# lpm.net
KiCad netlist of a schematic drawn in EAGLE
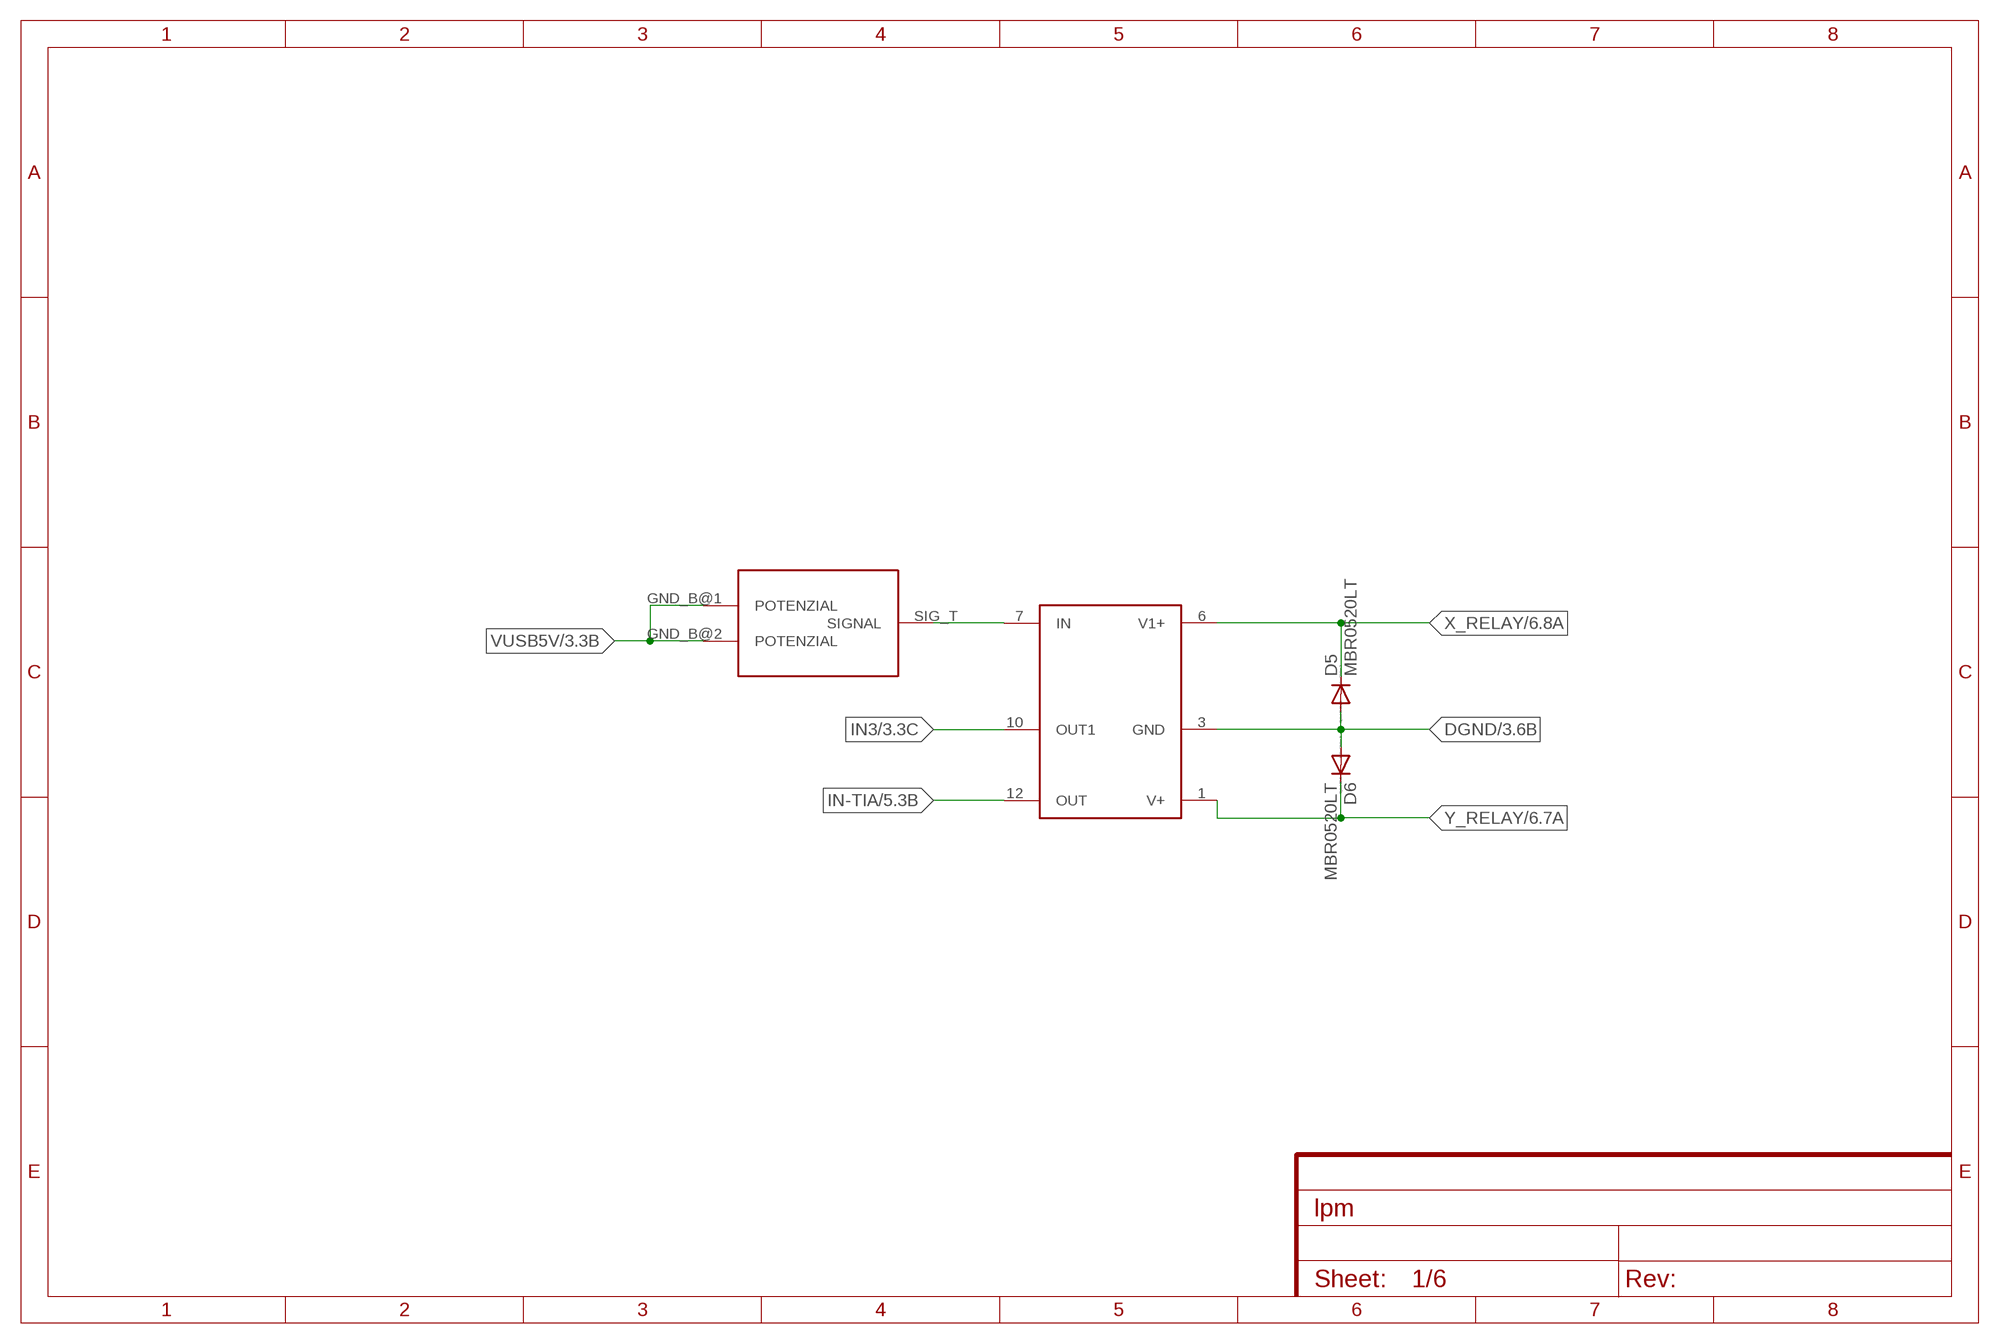
[diagram p0: schematic, sheet 1]
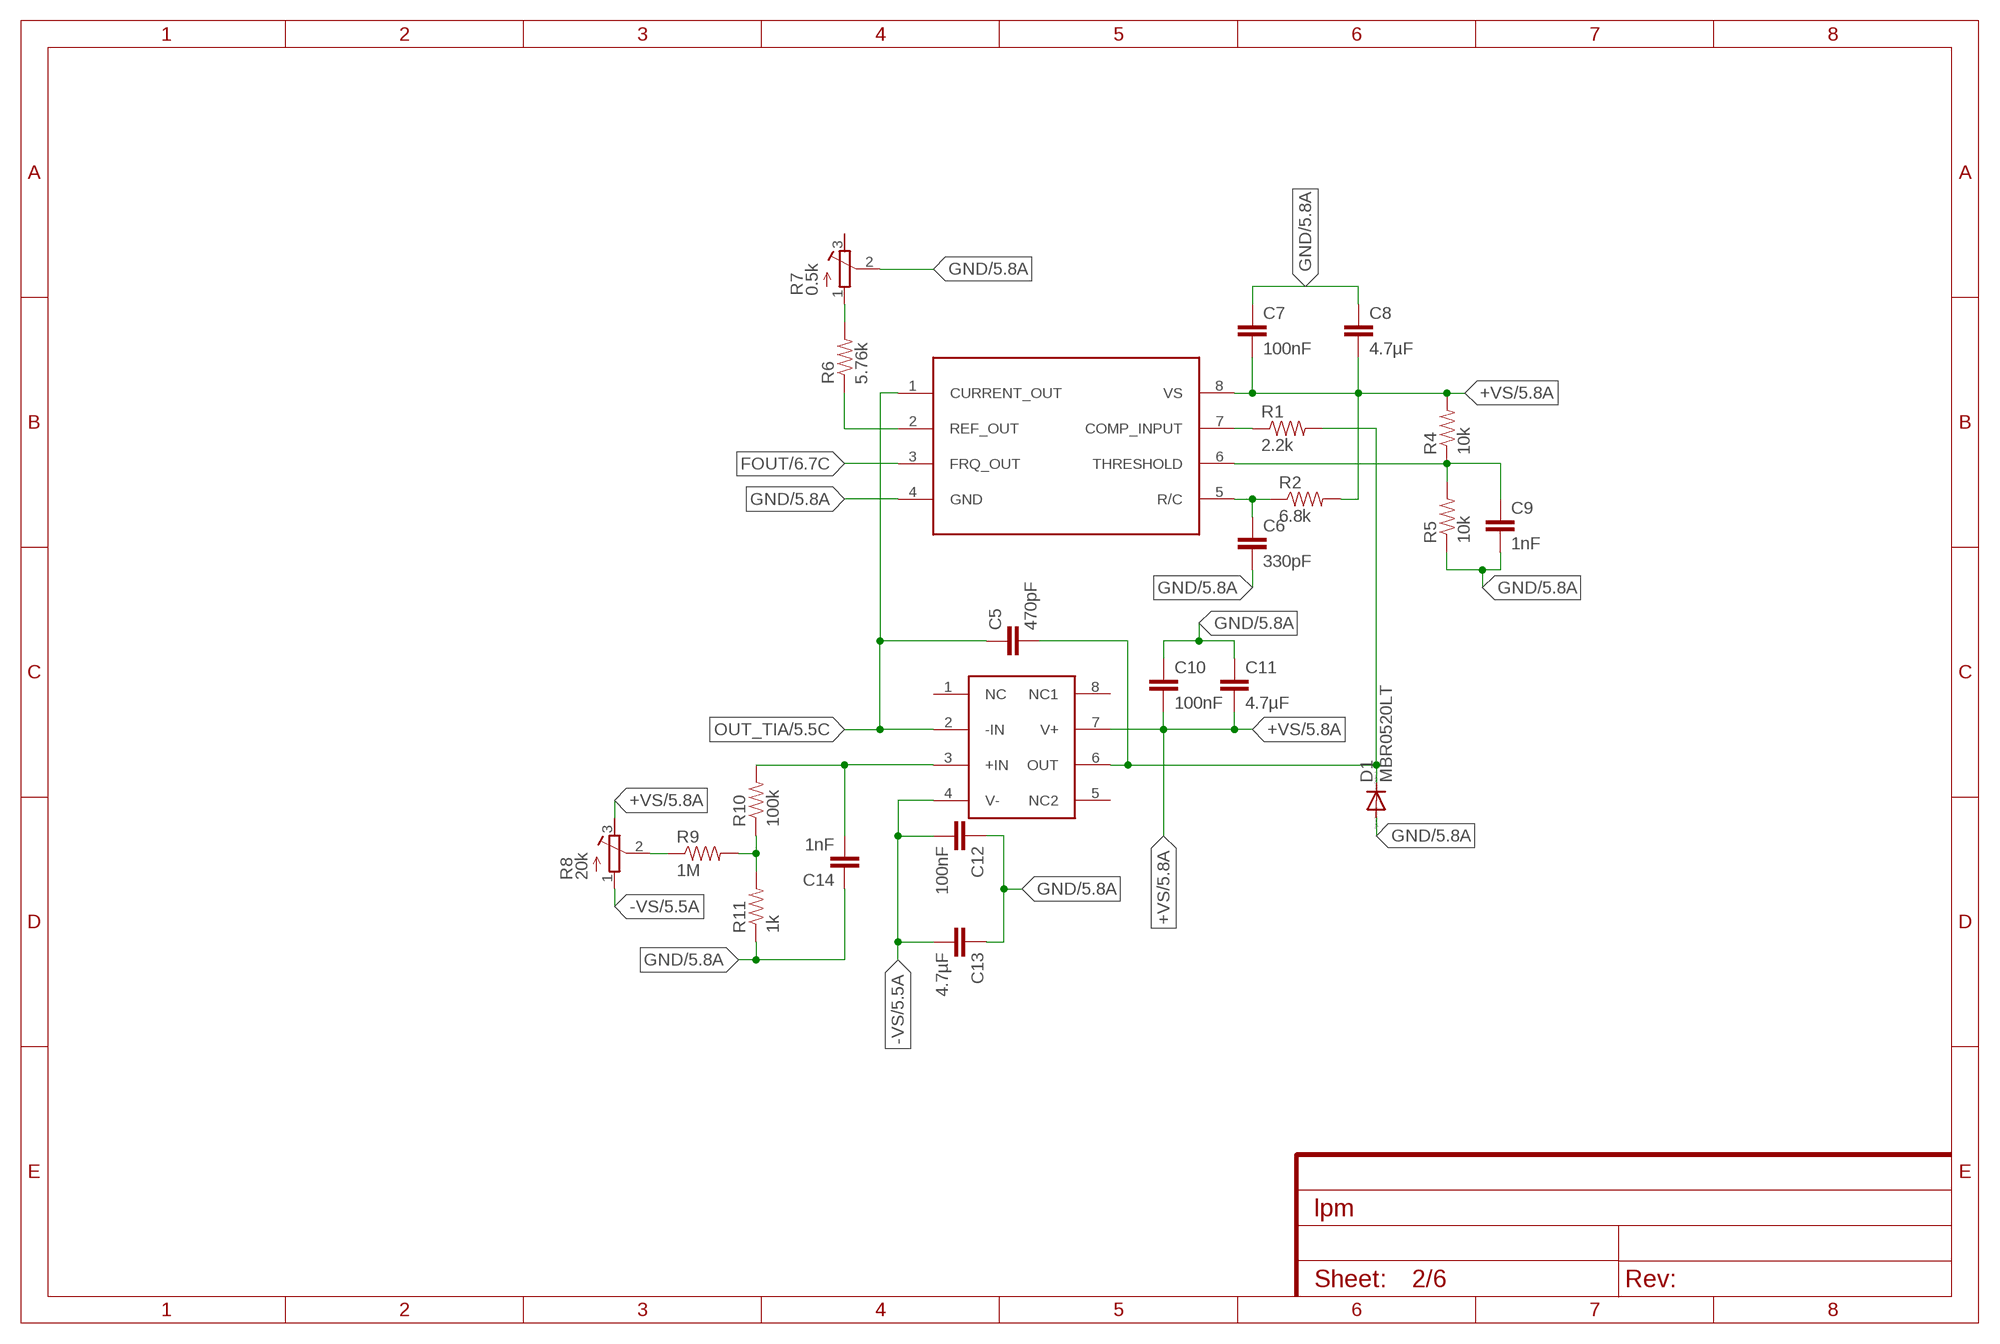
[diagram p1: schematic, sheet 2]
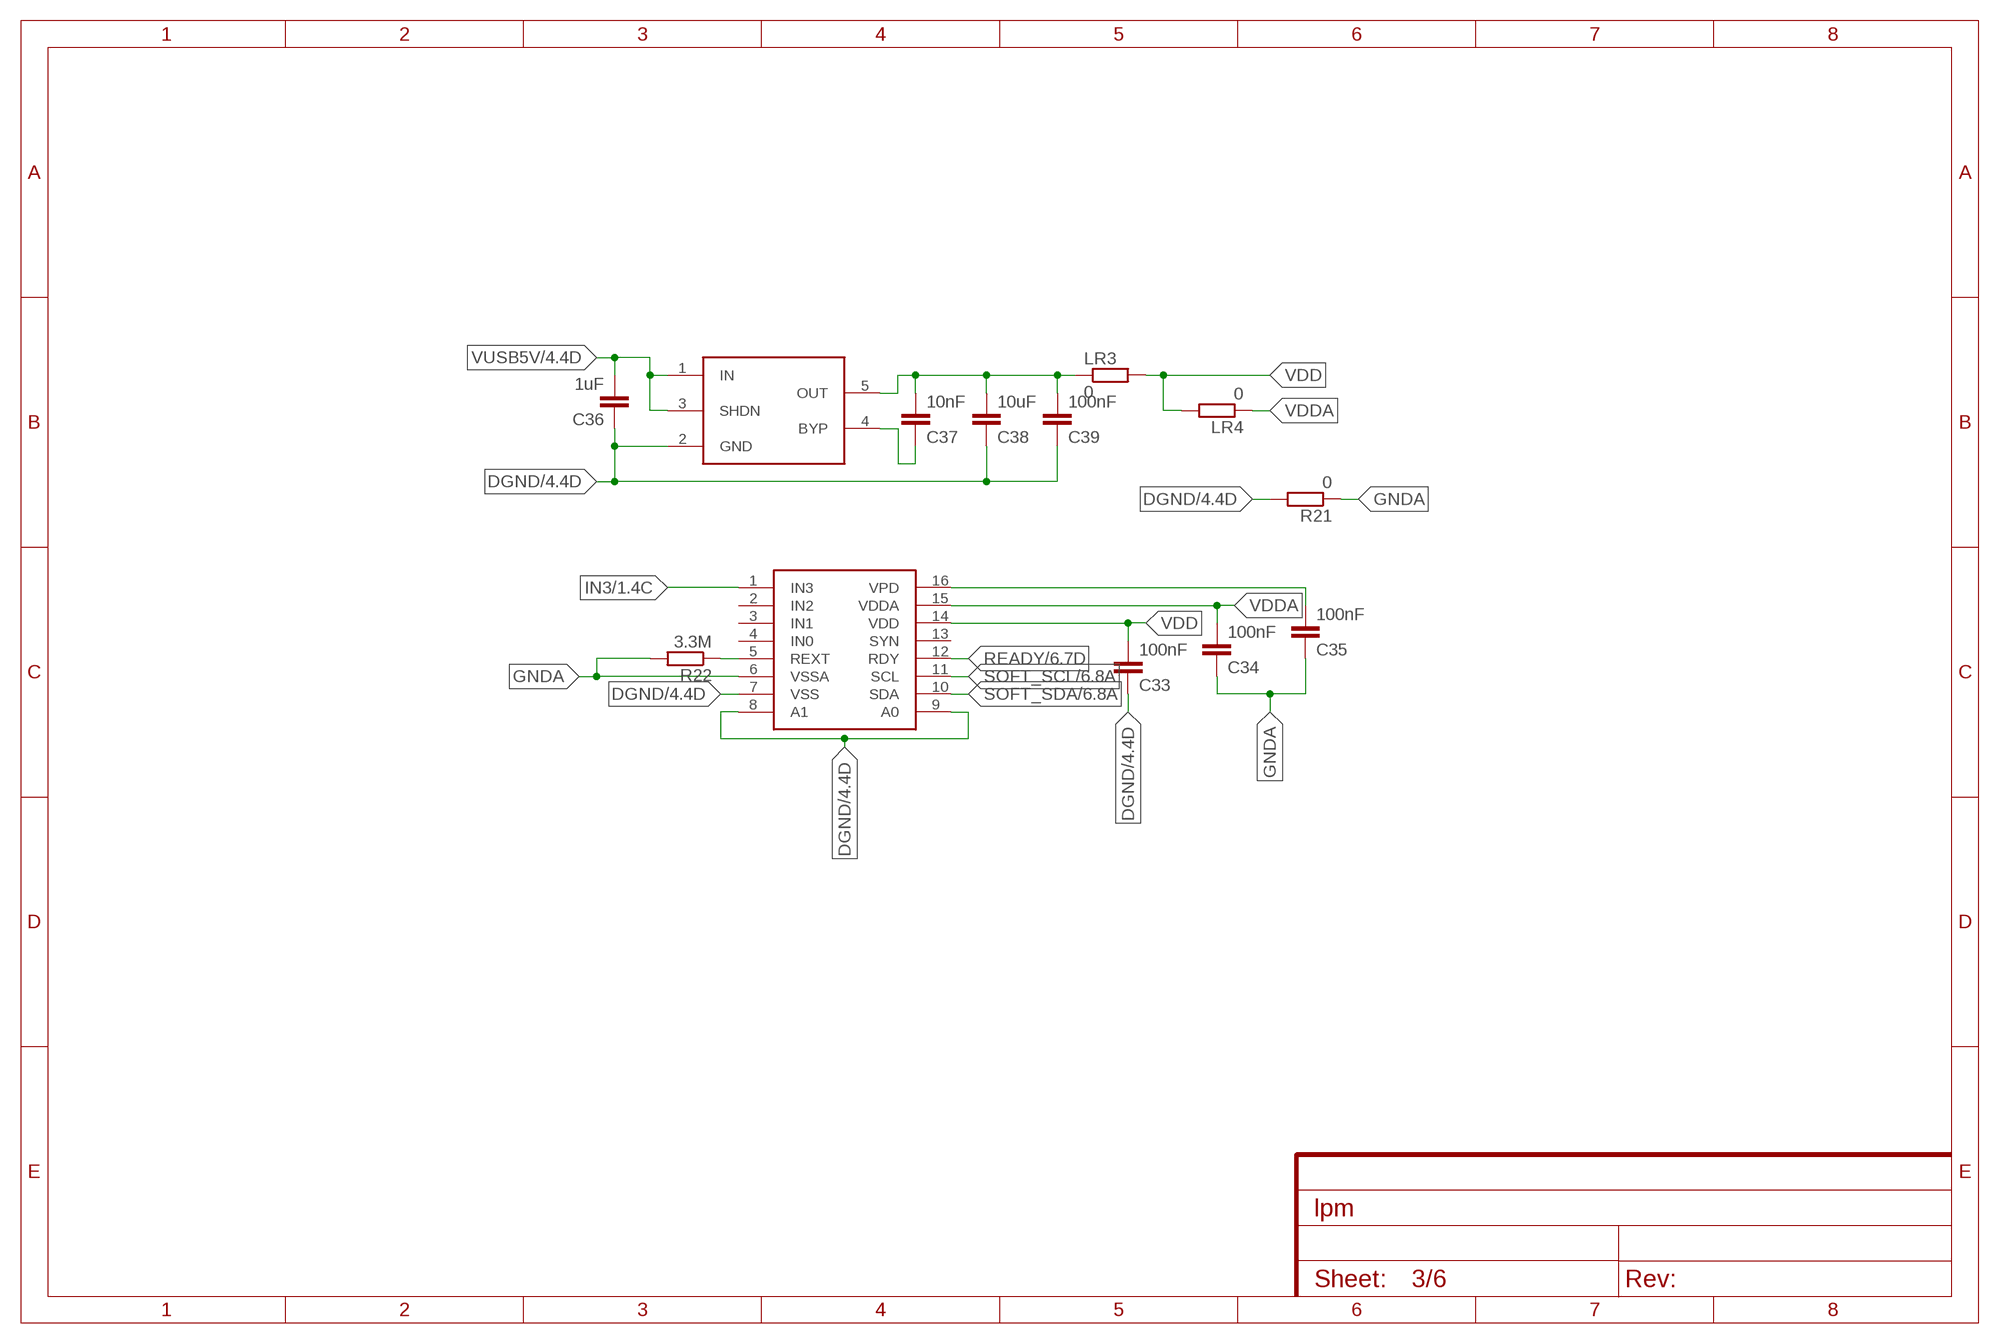
[diagram p2: schematic, sheet 3]
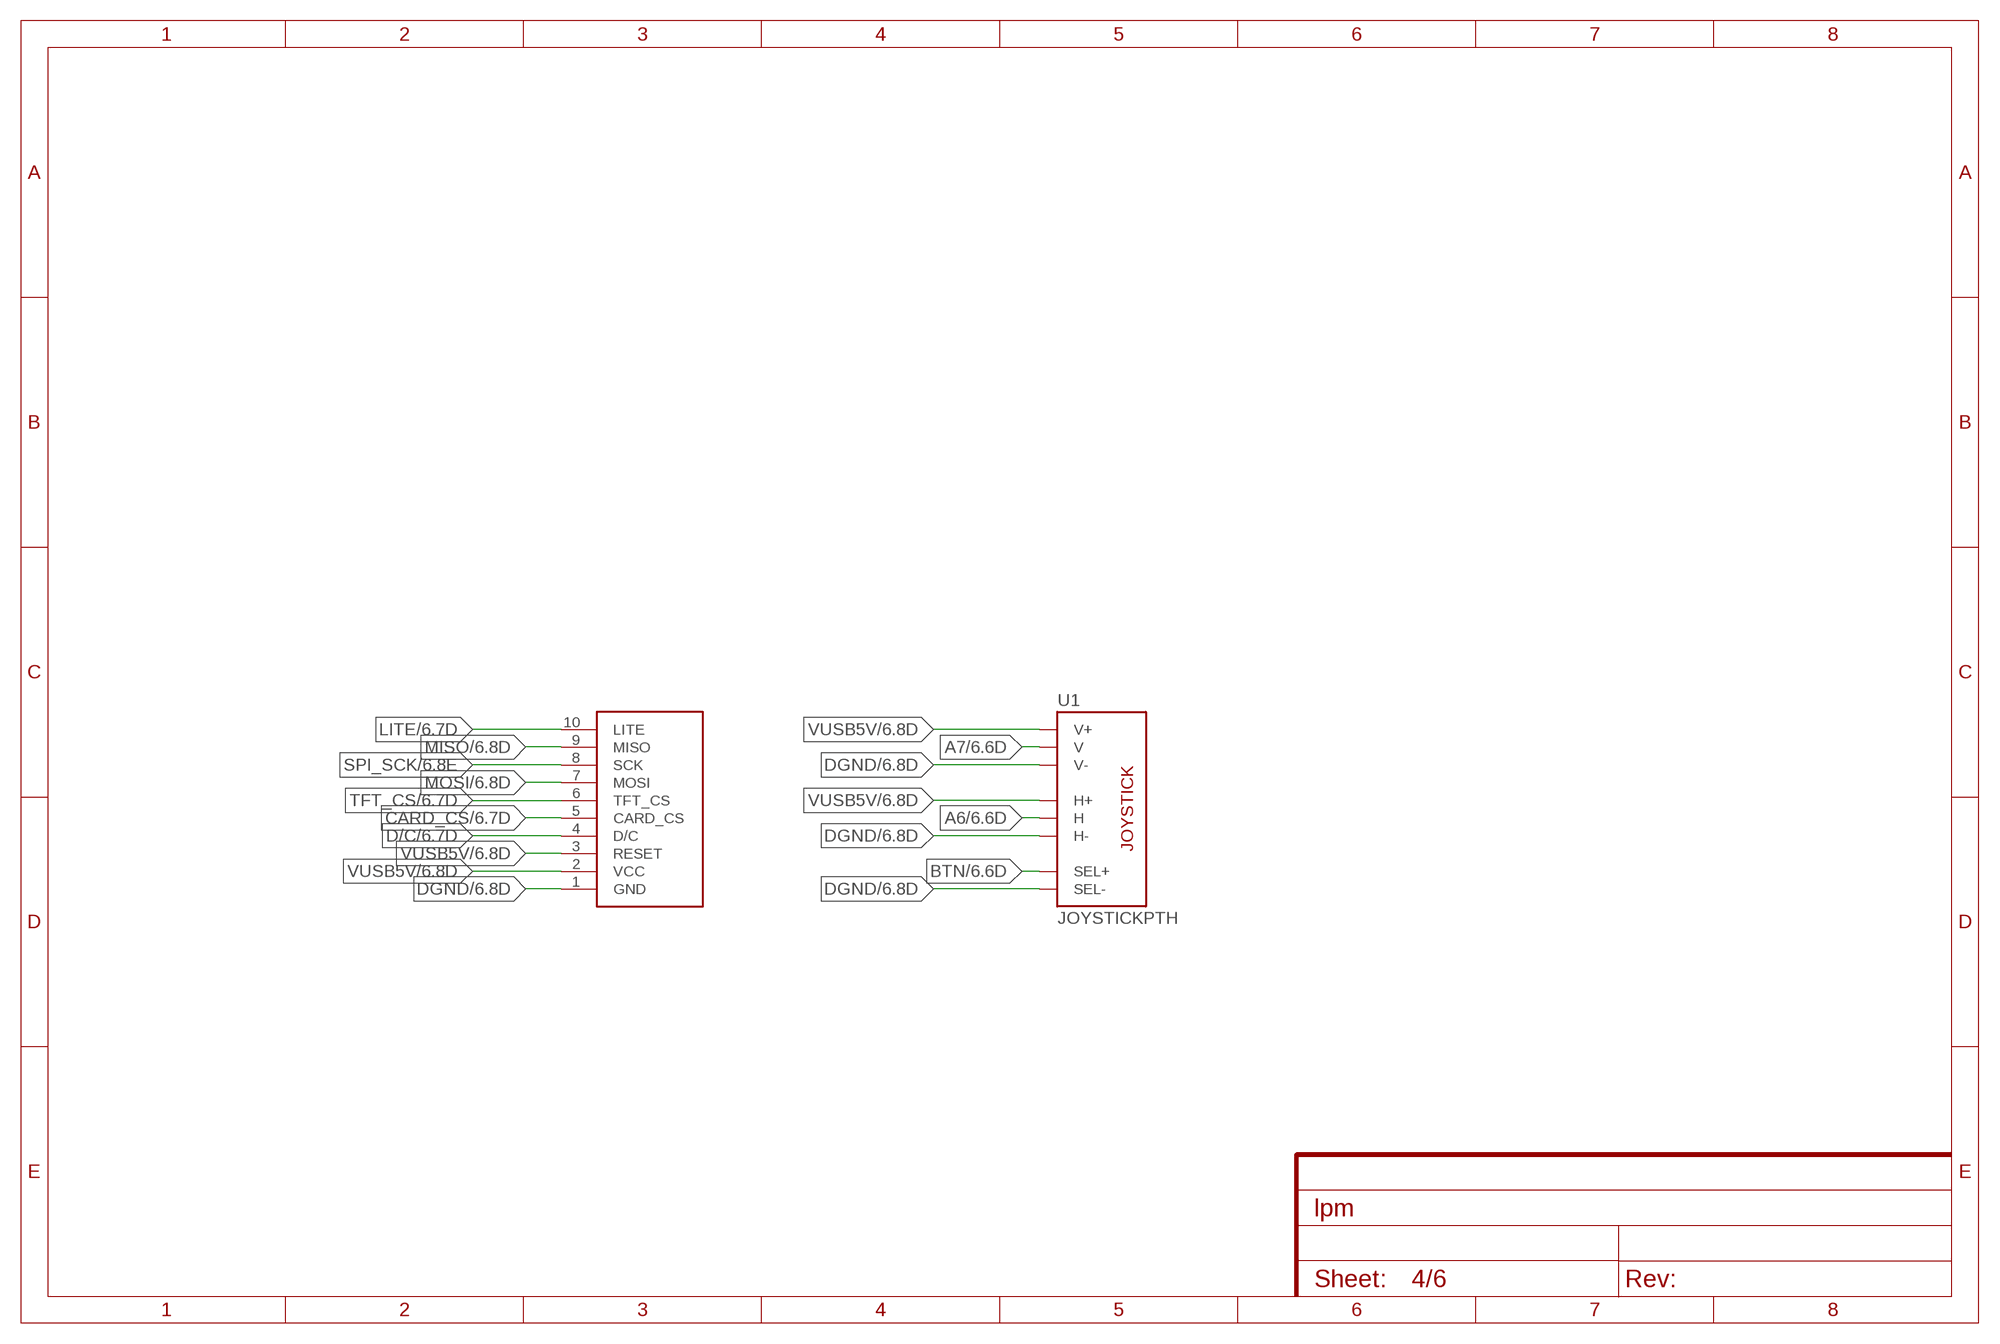
[diagram p3: schematic, sheet 4]
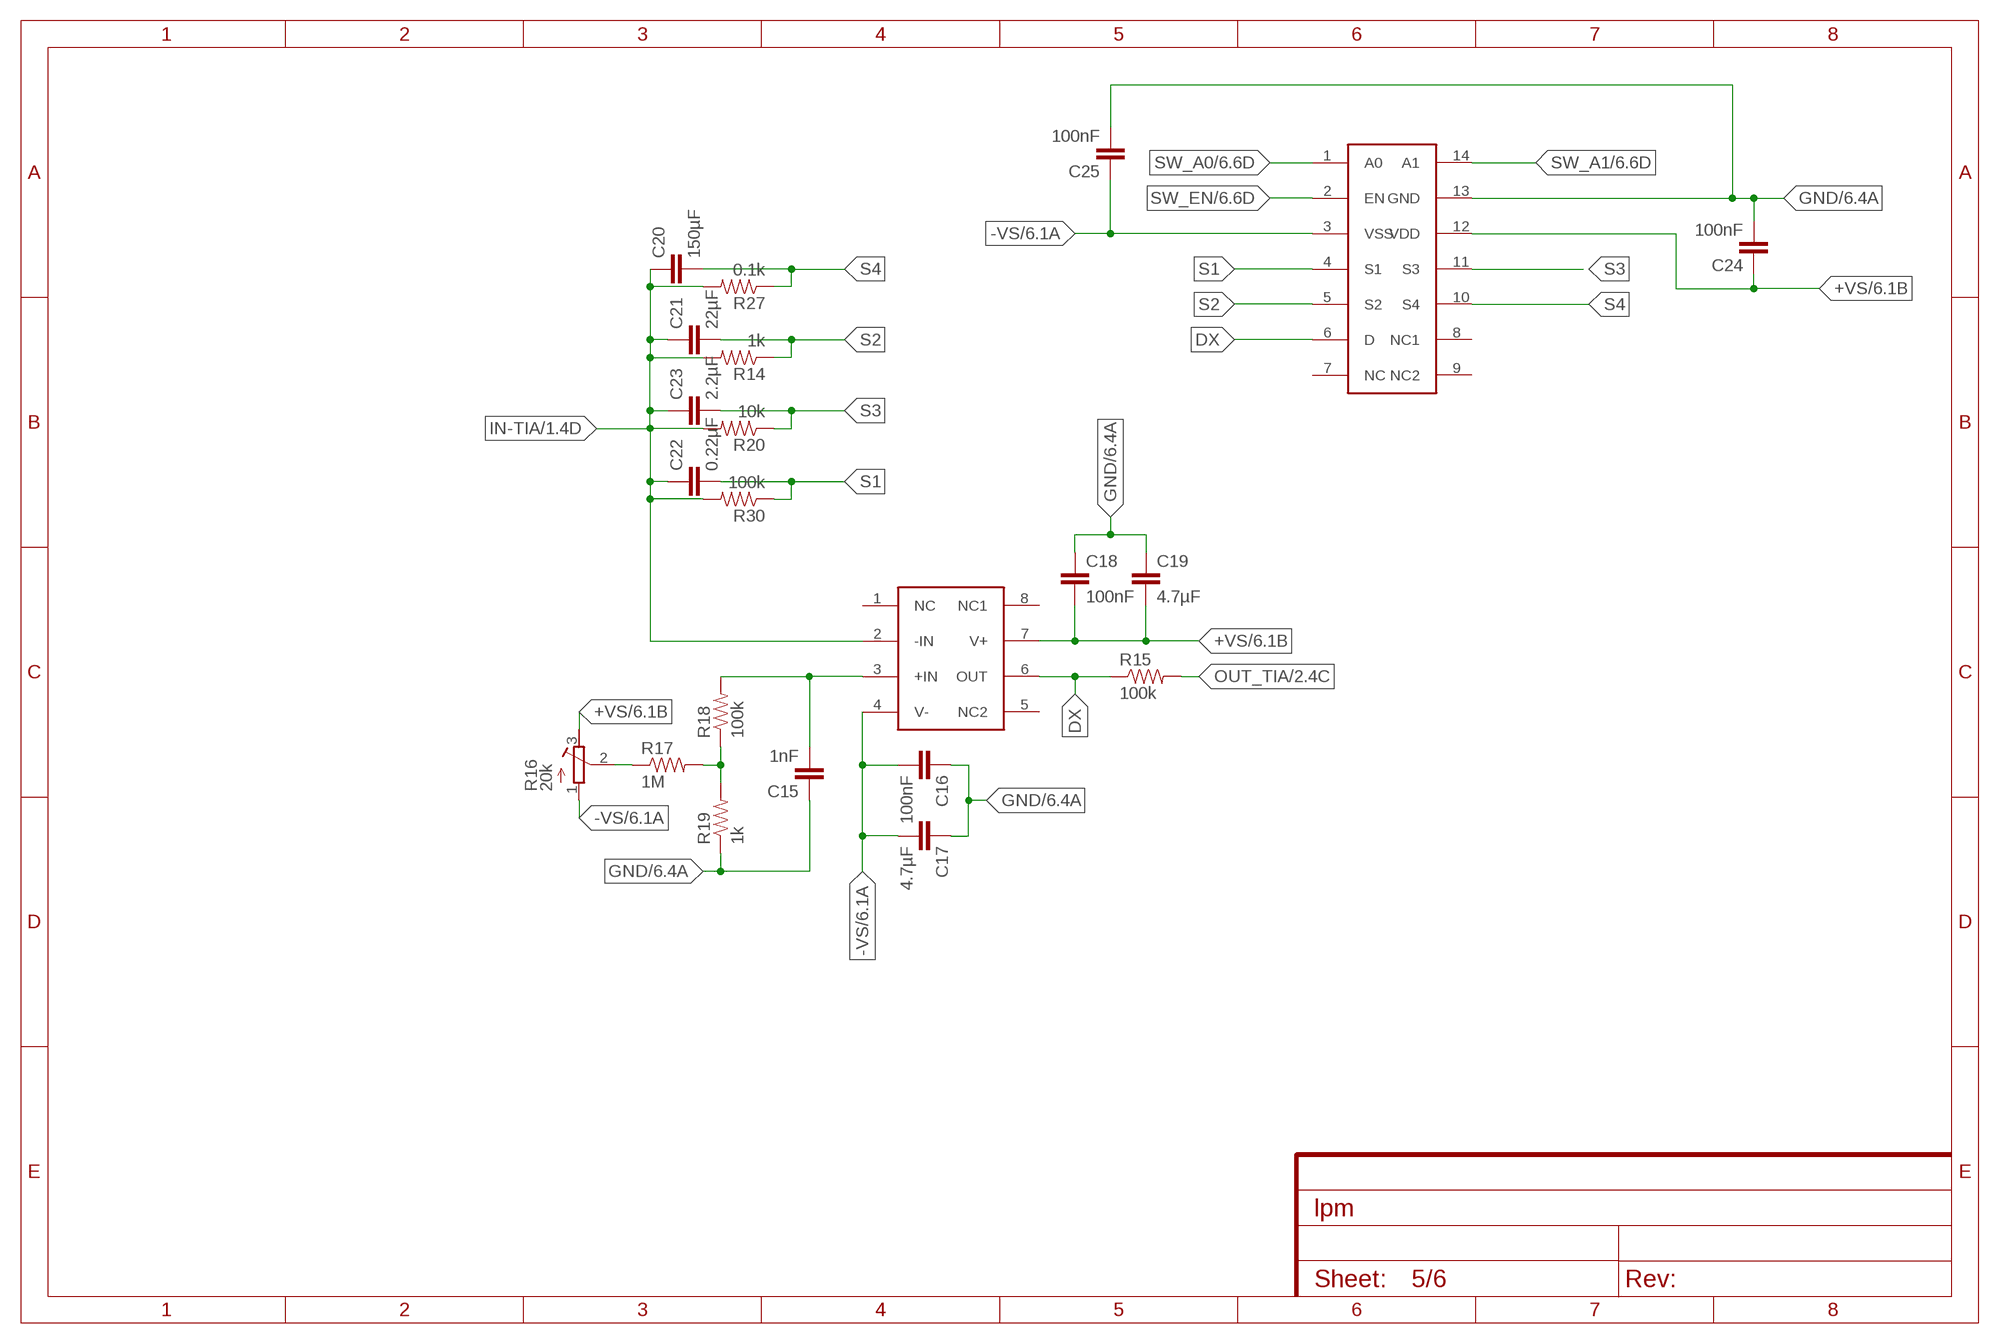
[diagram p4: schematic, sheet 5]
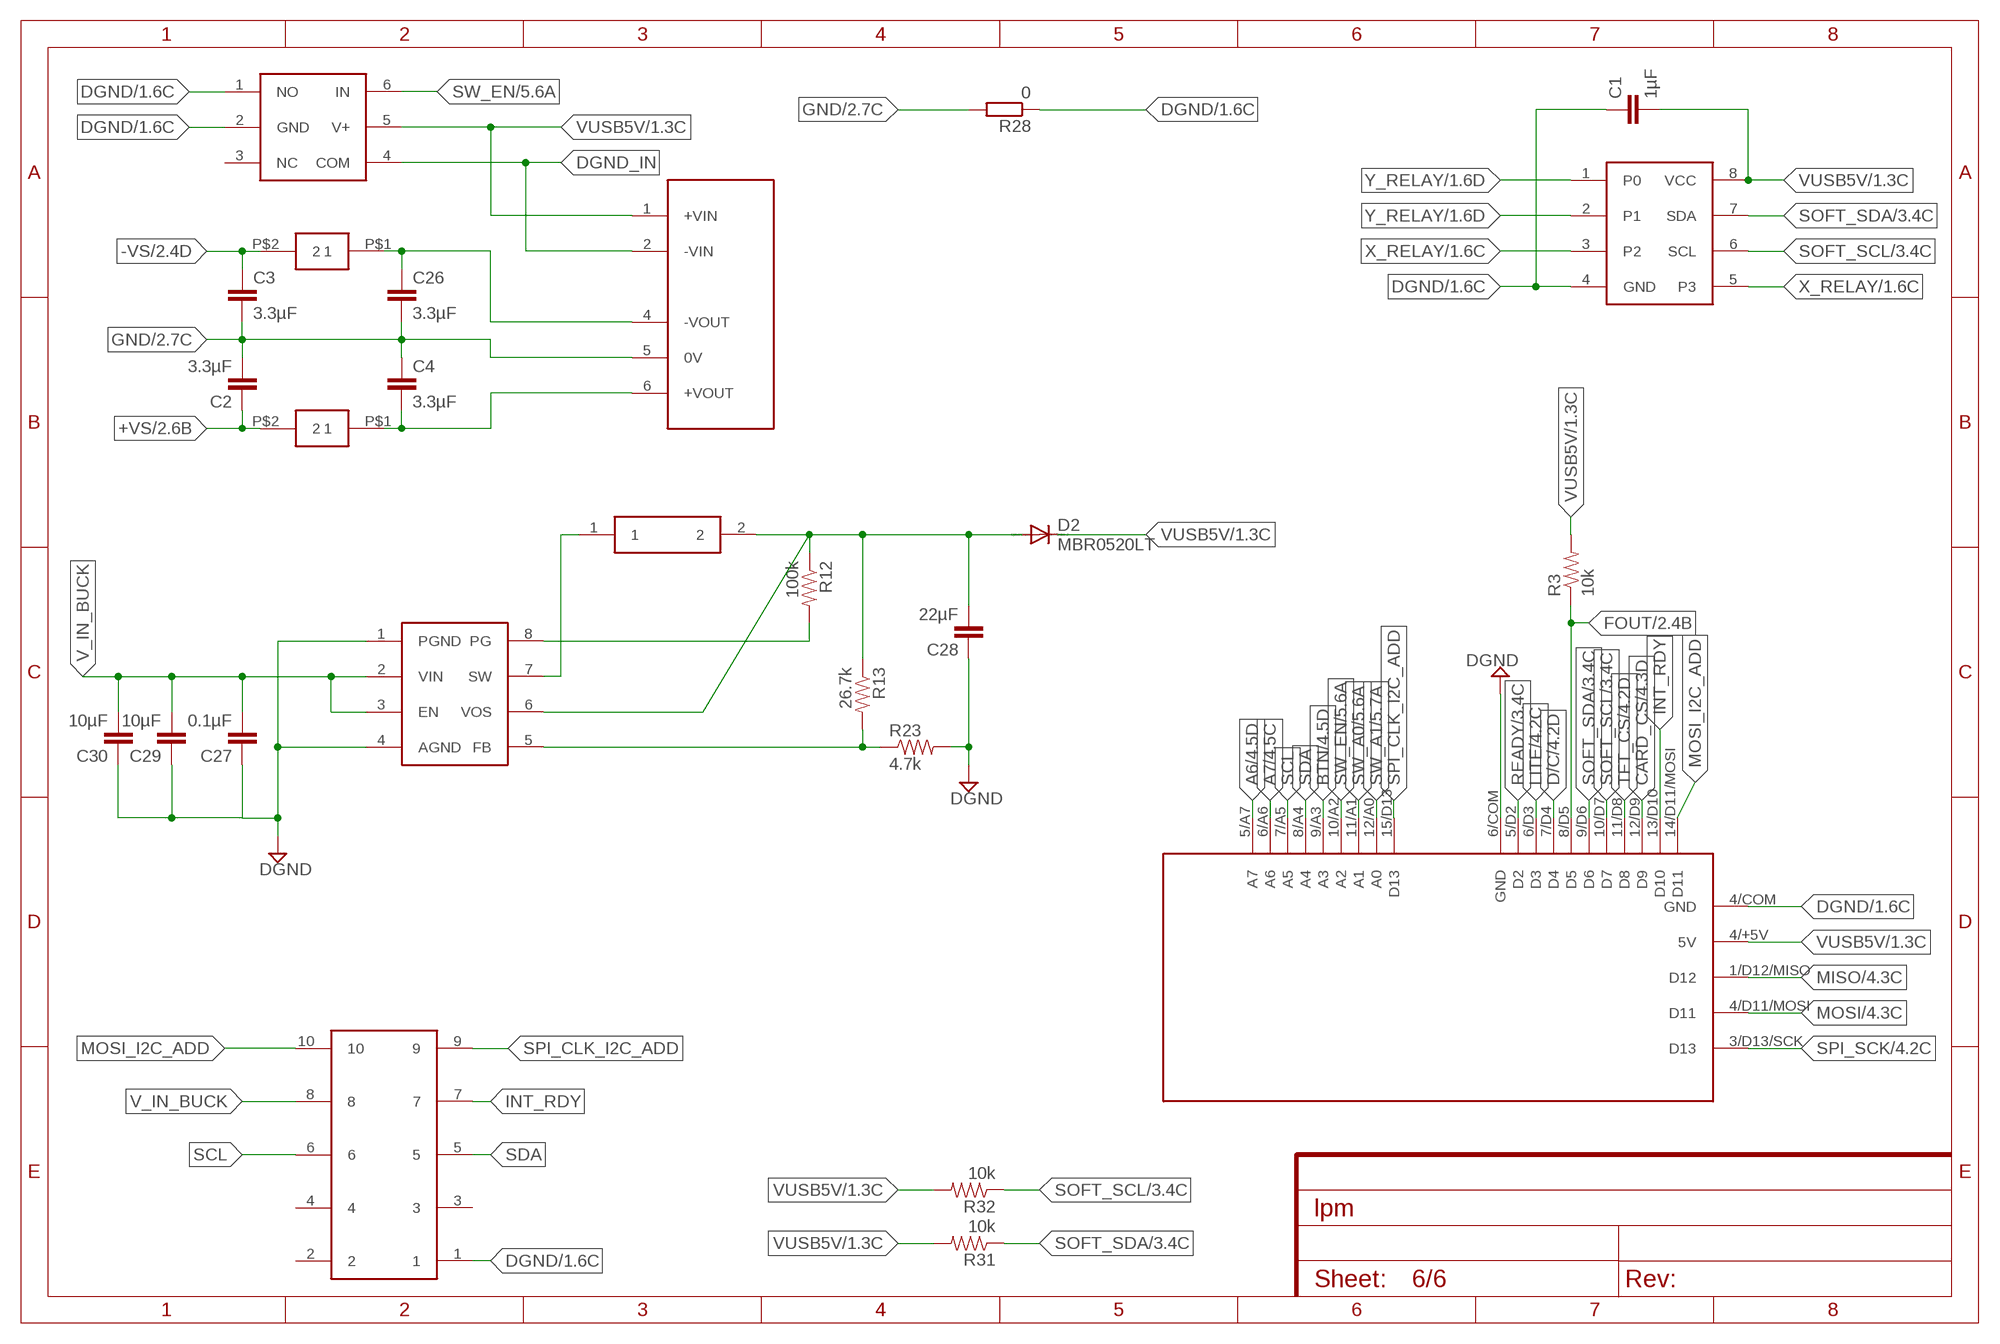
[diagram p5: schematic, sheet 6]

(export (version "E")
  (design (tool "Eeschema 10.0.6"))
  (components
    (comp (ref "C1")
      (value "1µF")
      (footprint "eagle-import:C0603K")
      (libsource (lib "eagle-import") (part "C-EUC0603K"))
    )
    (comp (ref "C2")
      (value "3.3µF")
      (footprint "eagle-import:C0603K")
      (libsource (lib "eagle-import") (part "C-EUC0603K"))
    )
    (comp (ref "C3")
      (value "3.3µF")
      (footprint "eagle-import:C0603K")
      (libsource (lib "eagle-import") (part "C-EUC0603K"))
    )
    (comp (ref "C4")
      (value "3.3µF")
      (footprint "eagle-import:C0603K")
      (libsource (lib "eagle-import") (part "C-EUC0603K"))
    )
    (comp (ref "C26")
      (value "3.3µF")
      (footprint "eagle-import:C0603K")
      (libsource (lib "eagle-import") (part "C-EUC0603K"))
    )
    (comp (ref "C27")
      (value "0.1µF")
      (footprint "eagle-import:C0603K")
      (libsource (lib "eagle-import") (part "C-EUC0603K"))
    )
    (comp (ref "C28")
      (value "22µF")
      (footprint "eagle-import:C0603K")
      (libsource (lib "eagle-import") (part "C-EUC0603K"))
    )
    (comp (ref "C29")
      (value "10µF")
      (footprint "eagle-import:C0603K")
      (libsource (lib "eagle-import") (part "C-EUC0603K"))
    )
    (comp (ref "C30")
      (value "10µF")
      (footprint "eagle-import:C0603K")
      (libsource (lib "eagle-import") (part "C-EUC0603K"))
    )
    (comp (ref "D2")
      (value "MBR0520LT")
      (footprint "eagle-import:SOD123")
      (libsource (lib "eagle-import") (part "MBR0520LT"))
    )
    (comp (ref "R3")
      (value "10k")
      (footprint "eagle-import:0603-RES")
      (libsource (lib "eagle-import") (part "RESISTOR0603-RES"))
    )
    (comp (ref "R12")
      (value "100k")
      (footprint "eagle-import:0603-RES")
      (libsource (lib "eagle-import") (part "RESISTOR0603-RES"))
    )
    (comp (ref "R13")
      (value "26.7k")
      (footprint "eagle-import:0603-RES")
      (libsource (lib "eagle-import") (part "RESISTOR0603-RES"))
    )
    (comp (ref "R23")
      (value "4.7k")
      (footprint "eagle-import:0603-RES")
      (libsource (lib "eagle-import") (part "RESISTOR0603-RES"))
    )
    (comp (ref "R28")
      (value "0")
      (footprint "eagle-import:R0603")
      (libsource (lib "eagle-import") (part "resistor_R-EU_R0603"))
    )
    (comp (ref "R31")
      (value "10k")
      (footprint "eagle-import:0603-RES")
      (libsource (lib "eagle-import") (part "RESISTOR0603-RES"))
    )
    (comp (ref "R32")
      (value "10k")
      (footprint "eagle-import:0603-RES")
      (libsource (lib "eagle-import") (part "RESISTOR0603-RES"))
    )
    (comp (ref "U$2")
      (value "KMP_100µH")
      (footprint "eagle-import:KMP")
      (libsource (lib "eagle-import") (part "KMP"))
    )
    (comp (ref "U$3")
      (value "HEADER_10POL")
      (footprint "eagle-import:BOX_HEADER_2.54MM")
      (libsource (lib "eagle-import") (part "HEADER_10POL"))
    )
    (comp (ref "U$4")
      (value "KMP_100µH")
      (footprint "eagle-import:KMP")
      (libsource (lib "eagle-import") (part "KMP"))
    )
    (comp (ref "U$6")
      (value "TS5A3159A")
      (footprint "eagle-import:SOT23-6")
      (libsource (lib "eagle-import") (part "TS5A3159A"))
    )
    (comp (ref "U$7")
      (value "0")
      (footprint "eagle-import:SOIC8_4.90MMX3.91MM")
      (libsource (lib "eagle-import") (part "PCA9536"))
    )
    (comp (ref "U$9")
      (value "LPS3015")
      (footprint "eagle-import:LPS3015")
      (libsource (lib "eagle-import") (part "LPS3015"))
    )
    (comp (ref "U$11")
      (value "NMA0515SC")
      (footprint "eagle-import:SIP7")
      (libsource (lib "eagle-import") (part "NMA0515SC"))
    )
    (comp (ref "U$13")
      (value "NANO_V2")
      (footprint "eagle-import:NANO_V2")
      (libsource (lib "eagle-import") (part "NANO_V2"))
    )
    (comp (ref "U$14")
      (value "TPS62160")
      (footprint "eagle-import:POWER-SOP8")
      (libsource (lib "eagle-import") (part "TPS62160"))
    )
    (comp (ref "C15")
      (value "1nF")
      (footprint "eagle-import:C0603K")
      (libsource (lib "eagle-import") (part "C-EUC0603K"))
    )
    (comp (ref "C16")
      (value "100nF")
      (footprint "eagle-import:C0603K")
      (libsource (lib "eagle-import") (part "C-EUC0603K"))
    )
    (comp (ref "C17")
      (value "4.7µF")
      (footprint "eagle-import:C0603K")
      (libsource (lib "eagle-import") (part "C-EUC0603K"))
    )
    (comp (ref "C18")
      (value "100nF")
      (footprint "eagle-import:C0603K")
      (libsource (lib "eagle-import") (part "C-EUC0603K"))
    )
    (comp (ref "C19")
      (value "4.7µF")
      (footprint "eagle-import:C0603K")
      (libsource (lib "eagle-import") (part "C-EUC0603K"))
    )
    (comp (ref "C20")
      (value "150µF")
      (footprint "eagle-import:C1206")
      (libsource (lib "eagle-import") (part "C-EUC1206"))
    )
    (comp (ref "C21")
      (value "22µF")
      (footprint "eagle-import:C0805")
      (libsource (lib "eagle-import") (part "C-EUC0805"))
    )
    (comp (ref "C22")
      (value "0.22µF")
      (footprint "eagle-import:C0603")
      (libsource (lib "eagle-import") (part "C-EUC0603"))
    )
    (comp (ref "C23")
      (value "2.2µF")
      (footprint "eagle-import:C0805")
      (libsource (lib "eagle-import") (part "C-EUC0805"))
    )
    (comp (ref "C24")
      (value "100nF")
      (footprint "eagle-import:C0603K")
      (libsource (lib "eagle-import") (part "C-EUC0603K"))
    )
    (comp (ref "C25")
      (value "100nF")
      (footprint "eagle-import:C0603K")
      (libsource (lib "eagle-import") (part "C-EUC0603K"))
    )
    (comp (ref "R14")
      (value "1k")
      (footprint "eagle-import:0603-RES")
      (libsource (lib "eagle-import") (part "RESISTOR0603-RES"))
    )
    (comp (ref "R15")
      (value "100k")
      (footprint "eagle-import:0603-RES")
      (libsource (lib "eagle-import") (part "RESISTOR0603-RES"))
    )
    (comp (ref "R16")
      (value "20k")
      (footprint "eagle-import:RTRIMTS63Y")
      (libsource (lib "eagle-import") (part "R-TRIMMTS63Y"))
    )
    (comp (ref "R17")
      (value "1M")
      (footprint "eagle-import:0603-RES")
      (libsource (lib "eagle-import") (part "RESISTOR0603-RES"))
    )
    (comp (ref "R18")
      (value "100k")
      (footprint "eagle-import:0603-RES")
      (libsource (lib "eagle-import") (part "RESISTOR0603-RES"))
    )
    (comp (ref "R19")
      (value "1k")
      (footprint "eagle-import:0603-RES")
      (libsource (lib "eagle-import") (part "RESISTOR0603-RES"))
    )
    (comp (ref "R20")
      (value "10k")
      (footprint "eagle-import:0603-RES")
      (libsource (lib "eagle-import") (part "RESISTOR0603-RES"))
    )
    (comp (ref "R27")
      (value "0.1k")
      (footprint "eagle-import:1206")
      (libsource (lib "eagle-import") (part "RESISTOR1206"))
    )
    (comp (ref "R30")
      (value "100k")
      (footprint "eagle-import:0603-RES")
      (libsource (lib "eagle-import") (part "RESISTOR0603-RES"))
    )
    (comp (ref "U$1")
      (value "ADG1404")
      (footprint "eagle-import:TSSOP14-0.65-5X4.4MM")
      (libsource (lib "eagle-import") (part "ADG1404"))
    )
    (comp (ref "U$12")
      (value "OPA191")
      (footprint "eagle-import:SOIC8_4.90MMX3.91MM")
      (libsource (lib "eagle-import") (part "OPA191"))
    )
    (comp (ref "C33")
      (value "100nF")
      (footprint "eagle-import:C0603")
      (libsource (lib "eagle-import") (part "C-EUC0603"))
    )
    (comp (ref "C34")
      (value "100nF")
      (footprint "eagle-import:C0603")
      (libsource (lib "eagle-import") (part "C-EUC0603"))
    )
    (comp (ref "C35")
      (value "100nF")
      (footprint "eagle-import:C0603")
      (libsource (lib "eagle-import") (part "C-EUC0603"))
    )
    (comp (ref "C36")
      (value "1uF")
      (footprint "eagle-import:C0603")
      (libsource (lib "eagle-import") (part "C-EUC0603"))
    )
    (comp (ref "C37")
      (value "10nF")
      (footprint "eagle-import:C0603")
      (libsource (lib "eagle-import") (part "C-EUC0603"))
    )
    (comp (ref "C38")
      (value "10uF")
      (footprint "eagle-import:C0603")
      (libsource (lib "eagle-import") (part "C-EUC0603"))
    )
    (comp (ref "C39")
      (value "100nF")
      (footprint "eagle-import:C0603")
      (libsource (lib "eagle-import") (part "C-EUC0603"))
    )
    (comp (ref "LDO1")
      (value "LT1761")
      (footprint "eagle-import:TSOT23-5")
      (libsource (lib "eagle-import") (part "LT1761"))
    )
    (comp (ref "LR3")
      (value "0")
      (footprint "eagle-import:R0603")
      (libsource (lib "eagle-import") (part "R-EU_R0603"))
    )
    (comp (ref "LR4")
      (value "0")
      (footprint "eagle-import:R0603")
      (libsource (lib "eagle-import") (part "R-EU_R0603"))
    )
    (comp (ref "MCDC01")
      (value "MCDC04")
      (footprint "eagle-import:SSOP16")
      (libsource (lib "eagle-import") (part "MCDC04"))
    )
    (comp (ref "R21")
      (value "0")
      (footprint "eagle-import:R0603")
      (libsource (lib "eagle-import") (part "R-EU_R0603"))
    )
    (comp (ref "R22")
      (value "3.3M")
      (footprint "eagle-import:R0603")
      (libsource (lib "eagle-import") (part "R-EU_R0603"))
    )
    (comp (ref "D5")
      (value "MBR0520LT")
      (footprint "eagle-import:SOD123")
      (libsource (lib "eagle-import") (part "MBR0520LT"))
    )
    (comp (ref "D6")
      (value "MBR0520LT")
      (footprint "eagle-import:SOD123")
      (libsource (lib "eagle-import") (part "MBR0520LT"))
    )
    (comp (ref "RELAY")
      (value "DS1E")
      (footprint "eagle-import:DIP12_8MM_X_13MM_DS1E")
      (libsource (lib "eagle-import") (part "DS1E"))
    )
    (comp (ref "U$8")
      (value "SMA_RAND")
      (footprint "eagle-import:SMA-RAND-PRINT")
      (libsource (lib "eagle-import") (part "SMA_RAND"))
    )
    (comp (ref "C5")
      (value "470pF")
      (footprint "eagle-import:0603-CAP")
      (libsource (lib "eagle-import") (part "CAP0603-CAP"))
    )
    (comp (ref "C6")
      (value "330pF")
      (footprint "eagle-import:C0603K")
      (libsource (lib "eagle-import") (part "C-EUC0603K"))
    )
    (comp (ref "C7")
      (value "100nF")
      (footprint "eagle-import:C0603K")
      (libsource (lib "eagle-import") (part "C-EUC0603K"))
    )
    (comp (ref "C8")
      (value "4.7µF")
      (footprint "eagle-import:C0603K")
      (libsource (lib "eagle-import") (part "C-EUC0603K"))
    )
    (comp (ref "C9")
      (value "1nF")
      (footprint "eagle-import:C0603K")
      (libsource (lib "eagle-import") (part "C-EUC0603K"))
    )
    (comp (ref "C10")
      (value "100nF")
      (footprint "eagle-import:C0603K")
      (libsource (lib "eagle-import") (part "C-EUC0603K"))
    )
    (comp (ref "C11")
      (value "4.7µF")
      (footprint "eagle-import:C0603K")
      (libsource (lib "eagle-import") (part "C-EUC0603K"))
    )
    (comp (ref "C12")
      (value "100nF")
      (footprint "eagle-import:C0603K")
      (libsource (lib "eagle-import") (part "C-EUC0603K"))
    )
    (comp (ref "C13")
      (value "4.7µF")
      (footprint "eagle-import:C0603K")
      (libsource (lib "eagle-import") (part "C-EUC0603K"))
    )
    (comp (ref "C14")
      (value "1nF")
      (footprint "eagle-import:C0603K")
      (libsource (lib "eagle-import") (part "C-EUC0603K"))
    )
    (comp (ref "D1")
      (value "MBR0520LT")
      (footprint "eagle-import:SOD123")
      (libsource (lib "eagle-import") (part "MBR0520LT"))
    )
    (comp (ref "R1")
      (value "2.2k")
      (footprint "eagle-import:0603-RES")
      (libsource (lib "eagle-import") (part "RESISTOR0603-RES"))
    )
    (comp (ref "R2")
      (value "6.8k")
      (footprint "eagle-import:0805")
      (libsource (lib "eagle-import") (part "RESISTOR0805-RES"))
    )
    (comp (ref "R4")
      (value "10k")
      (footprint "eagle-import:0603-RES")
      (libsource (lib "eagle-import") (part "RESISTOR0603-RES"))
    )
    (comp (ref "R5")
      (value "10k")
      (footprint "eagle-import:0603-RES")
      (libsource (lib "eagle-import") (part "RESISTOR0603-RES"))
    )
    (comp (ref "R6")
      (value "5.76k")
      (footprint "eagle-import:0603-RES")
      (libsource (lib "eagle-import") (part "RESISTOR0603-RES"))
    )
    (comp (ref "R7")
      (value "0.5k")
      (footprint "eagle-import:RTRIMTSM53YL")
      (libsource (lib "eagle-import") (part "R-TRIMMTSM53YL"))
    )
    (comp (ref "R8")
      (value "20k")
      (footprint "eagle-import:RTRIMTS63Y")
      (libsource (lib "eagle-import") (part "R-TRIMMTS63Y"))
    )
    (comp (ref "R9")
      (value "1M")
      (footprint "eagle-import:0603-RES")
      (libsource (lib "eagle-import") (part "RESISTOR0603-RES"))
    )
    (comp (ref "R10")
      (value "100k")
      (footprint "eagle-import:0603-RES")
      (libsource (lib "eagle-import") (part "RESISTOR0603-RES"))
    )
    (comp (ref "R11")
      (value "1k")
      (footprint "eagle-import:0603-RES")
      (libsource (lib "eagle-import") (part "RESISTOR0603-RES"))
    )
    (comp (ref "U$10")
      (value "OPA191")
      (footprint "eagle-import:SOIC8_4.90MMX3.91MM")
      (libsource (lib "eagle-import") (part "OPA191"))
    )
    (comp (ref "VFC")
      (value "LM331")
      (footprint "eagle-import:DIP-08")
      (libsource (lib "eagle-import") (part "LM331"))
    )
    (comp (ref "DISPLAY")
      (value "DISPLAY")
      (footprint "eagle-import:DISPLAY")
      (libsource (lib "eagle-import") (part "DISPLAY"))
    )
    (comp (ref "U1")
      (value "JOYSTICKPTH")
      (footprint "eagle-import:JOYSTICK")
      (libsource (lib "eagle-import") (part "JOYSTICKPTH"))
    )
  )
  (nets
    (net (code "1") (name "+VS") (class "Default")
      (node (ref "C10") (pin "2") (pinfunction "2_2") (pintype "passive"))
      (node (ref "C11") (pin "2") (pinfunction "2_2") (pintype "passive"))
      (node (ref "C18") (pin "2") (pinfunction "2_2") (pintype "passive"))
      (node (ref "C19") (pin "2") (pinfunction "2_2") (pintype "passive"))
      (node (ref "C2") (pin "1") (pinfunction "1_1") (pintype "passive"))
      (node (ref "C24") (pin "1") (pinfunction "1_1") (pintype "passive"))
      (node (ref "C7") (pin "2") (pinfunction "2_2") (pintype "passive"))
      (node (ref "C8") (pin "2") (pinfunction "2_2") (pintype "passive"))
      (node (ref "R16") (pin "3") (pinfunction "E_3") (pintype "passive"))
      (node (ref "R2") (pin "2") (pinfunction "2_2") (pintype "passive"))
      (node (ref "R4") (pin "2") (pinfunction "2_2") (pintype "passive"))
      (node (ref "R8") (pin "3") (pinfunction "E_3") (pintype "passive"))
      (node (ref "U$1") (pin "12") (pinfunction "VDD_12") (pintype "bidirectional"))
      (node (ref "U$10") (pin "7") (pinfunction "V+_7") (pintype "bidirectional"))
      (node (ref "U$12") (pin "7") (pinfunction "V+_7") (pintype "bidirectional"))
      (node (ref "U$4") (pin "P$2") (pinfunction "2_P$2") (pintype "bidirectional"))
      (node (ref "VFC") (pin "8") (pinfunction "VS_8") (pintype "bidirectional"))
    )
    (net (code "2") (name "-VS") (class "Default")
      (node (ref "C12") (pin "2") (pinfunction "2_2") (pintype "passive"))
      (node (ref "C13") (pin "2") (pinfunction "2_2") (pintype "passive"))
      (node (ref "C16") (pin "2") (pinfunction "2_2") (pintype "passive"))
      (node (ref "C17") (pin "2") (pinfunction "2_2") (pintype "passive"))
      (node (ref "C25") (pin "1") (pinfunction "1_1") (pintype "passive"))
      (node (ref "C3") (pin "1") (pinfunction "1_1") (pintype "passive"))
      (node (ref "R16") (pin "1") (pinfunction "A_1") (pintype "passive"))
      (node (ref "R8") (pin "1") (pinfunction "A_1") (pintype "passive"))
      (node (ref "U$1") (pin "3") (pinfunction "VSS_3") (pintype "bidirectional"))
      (node (ref "U$10") (pin "4") (pinfunction "V-_4") (pintype "bidirectional"))
      (node (ref "U$12") (pin "4") (pinfunction "V-_4") (pintype "bidirectional"))
      (node (ref "U$2") (pin "P$2") (pinfunction "2_P$2") (pintype "bidirectional"))
    )
    (net (code "3") (name "A6") (class "Default")
      (node (ref "U$13") (pin "5/A7") (pinfunction "A7_5/A7") (pintype "bidirectional"))
      (node (ref "U1") (pin "H2") (pinfunction "H_H2") (pintype "bidirectional"))
    )
    (net (code "4") (name "A7") (class "Default")
      (node (ref "U$13") (pin "6/A6") (pinfunction "A6_6/A6") (pintype "bidirectional"))
      (node (ref "U1") (pin "V2") (pinfunction "V_V2") (pintype "bidirectional"))
    )
    (net (code "5") (name "BTN") (class "Default")
      (node (ref "U$13") (pin "9/A3") (pinfunction "A3_9/A3") (pintype "bidirectional"))
      (node (ref "U1") (pin "B1A") (pinfunction "SEL+_B1A") (pintype "bidirectional"))
    )
    (net (code "6") (name "CARD_CS") (class "Default")
      (node (ref "DISPLAY") (pin "5") (pinfunction "CARD_CS_5") (pintype "bidirectional"))
      (node (ref "U$13") (pin "12/D9") (pinfunction "D9_12/D9") (pintype "bidirectional"))
    )
    (net (code "7") (name "DGND") (class "Default")
      (node (ref "C1") (pin "1") (pinfunction "1_1") (pintype "passive"))
      (node (ref "C27") (pin "1") (pinfunction "1_1") (pintype "passive"))
      (node (ref "C28") (pin "1") (pinfunction "1_1") (pintype "passive"))
      (node (ref "C29") (pin "1") (pinfunction "1_1") (pintype "passive"))
      (node (ref "C30") (pin "1") (pinfunction "1_1") (pintype "passive"))
      (node (ref "C33") (pin "1") (pinfunction "1_1") (pintype "passive"))
      (node (ref "C36") (pin "1") (pinfunction "1_1") (pintype "passive"))
      (node (ref "C38") (pin "1") (pinfunction "1_1") (pintype "passive"))
      (node (ref "C39") (pin "1") (pinfunction "1_1") (pintype "passive"))
      (node (ref "D5") (pin "A") (pinfunction "A_A") (pintype "passive"))
      (node (ref "D6") (pin "A") (pinfunction "A_A") (pintype "passive"))
      (node (ref "DISPLAY") (pin "1") (pinfunction "GND_1") (pintype "bidirectional"))
      (node (ref "LDO1") (pin "2") (pinfunction "GND_2") (pintype "bidirectional"))
      (node (ref "MCDC01") (pin "7") (pinfunction "VSS_7") (pintype "bidirectional"))
      (node (ref "MCDC01") (pin "8") (pinfunction "A1_8") (pintype "bidirectional"))
      (node (ref "MCDC01") (pin "9") (pinfunction "A0_9") (pintype "bidirectional"))
      (node (ref "R21") (pin "2") (pinfunction "2_2") (pintype "passive"))
      (node (ref "R23") (pin "2") (pinfunction "2_2") (pintype "passive"))
      (node (ref "R28") (pin "1") (pinfunction "1_1") (pintype "passive"))
      (node (ref "RELAY") (pin "3") (pinfunction "GND_3") (pintype "bidirectional"))
      (node (ref "U$13") (pin "4/COM") (pinfunction "GND_4/COM") (pintype "bidirectional"))
      (node (ref "U$13") (pin "6/COM") (pinfunction "GND_6/COM") (pintype "bidirectional"))
      (node (ref "U$14") (pin "1") (pinfunction "PGND_1") (pintype "bidirectional"))
      (node (ref "U$14") (pin "4") (pinfunction "AGND_4") (pintype "bidirectional"))
      (node (ref "U$3") (pin "1") (pinfunction "1_1") (pintype "bidirectional"))
      (node (ref "U$6") (pin "1") (pinfunction "NO_1") (pintype "bidirectional"))
      (node (ref "U$6") (pin "2") (pinfunction "GND_2") (pintype "bidirectional"))
      (node (ref "U$7") (pin "4") (pinfunction "GND_4") (pintype "bidirectional"))
      (node (ref "U1") (pin "B2A") (pinfunction "SEL-_B2A") (pintype "bidirectional"))
      (node (ref "U1") (pin "H3") (pinfunction "H-_H3") (pintype "bidirectional"))
      (node (ref "U1") (pin "V3") (pinfunction "V-_V3") (pintype "bidirectional"))
    )
    (net (code "8") (name "DGND_IN") (class "Default")
      (node (ref "U$11") (pin "2") (pinfunction "-VIN_2") (pintype "bidirectional"))
      (node (ref "U$6") (pin "4") (pinfunction "COM_4") (pintype "bidirectional"))
    )
    (net (code "9") (name "DX") (class "Default")
      (node (ref "R15") (pin "1") (pinfunction "1_1") (pintype "passive"))
      (node (ref "U$1") (pin "6") (pinfunction "D_6") (pintype "bidirectional"))
      (node (ref "U$12") (pin "6") (pinfunction "OUT_6") (pintype "bidirectional"))
    )
    (net (code "10") (name "D{slash}C") (class "Default")
      (node (ref "DISPLAY") (pin "4") (pinfunction "D/C_4") (pintype "bidirectional"))
      (node (ref "U$13") (pin "7/D4") (pinfunction "D4_7/D4") (pintype "bidirectional"))
    )
    (net (code "11") (name "FOUT") (class "Default")
      (node (ref "R3") (pin "1") (pinfunction "1_1") (pintype "passive"))
      (node (ref "U$13") (pin "8/D5") (pinfunction "D5_8/D5") (pintype "bidirectional"))
      (node (ref "VFC") (pin "3") (pinfunction "FRQ_OUT_3") (pintype "bidirectional"))
    )
    (net (code "12") (name "GND") (class "Default")
      (node (ref "C10") (pin "1") (pinfunction "1_1") (pintype "passive"))
      (node (ref "C11") (pin "1") (pinfunction "1_1") (pintype "passive"))
      (node (ref "C12") (pin "1") (pinfunction "1_1") (pintype "passive"))
      (node (ref "C13") (pin "1") (pinfunction "1_1") (pintype "passive"))
      (node (ref "C14") (pin "1") (pinfunction "1_1") (pintype "passive"))
      (node (ref "C15") (pin "1") (pinfunction "1_1") (pintype "passive"))
      (node (ref "C16") (pin "1") (pinfunction "1_1") (pintype "passive"))
      (node (ref "C17") (pin "1") (pinfunction "1_1") (pintype "passive"))
      (node (ref "C18") (pin "1") (pinfunction "1_1") (pintype "passive"))
      (node (ref "C19") (pin "1") (pinfunction "1_1") (pintype "passive"))
      (node (ref "C2") (pin "2") (pinfunction "2_2") (pintype "passive"))
      (node (ref "C24") (pin "2") (pinfunction "2_2") (pintype "passive"))
      (node (ref "C25") (pin "2") (pinfunction "2_2") (pintype "passive"))
      (node (ref "C26") (pin "2") (pinfunction "2_2") (pintype "passive"))
      (node (ref "C3") (pin "2") (pinfunction "2_2") (pintype "passive"))
      (node (ref "C4") (pin "1") (pinfunction "1_1") (pintype "passive"))
      (node (ref "C6") (pin "2") (pinfunction "2_2") (pintype "passive"))
      (node (ref "C7") (pin "1") (pinfunction "1_1") (pintype "passive"))
      (node (ref "C8") (pin "1") (pinfunction "1_1") (pintype "passive"))
      (node (ref "C9") (pin "2") (pinfunction "2_2") (pintype "passive"))
      (node (ref "D1") (pin "A") (pinfunction "A_A") (pintype "passive"))
      (node (ref "R11") (pin "1") (pinfunction "1_1") (pintype "passive"))
      (node (ref "R19") (pin "1") (pinfunction "1_1") (pintype "passive"))
      (node (ref "R28") (pin "2") (pinfunction "2_2") (pintype "passive"))
      (node (ref "R5") (pin "1") (pinfunction "1_1") (pintype "passive"))
      (node (ref "R7") (pin "2") (pinfunction "S_2") (pintype "passive"))
      (node (ref "U$1") (pin "13") (pinfunction "GND_13") (pintype "bidirectional"))
      (node (ref "U$11") (pin "5") (pinfunction "0V_5") (pintype "bidirectional"))
      (node (ref "VFC") (pin "4") (pinfunction "GND_4") (pintype "bidirectional"))
    )
    (net (code "13") (name "GNDA") (class "Default")
      (node (ref "C34") (pin "1") (pinfunction "1_1") (pintype "passive"))
      (node (ref "C35") (pin "1") (pinfunction "1_1") (pintype "passive"))
      (node (ref "MCDC01") (pin "6") (pinfunction "VSSA_6") (pintype "bidirectional"))
      (node (ref "R21") (pin "1") (pinfunction "1_1") (pintype "passive"))
      (node (ref "R22") (pin "2") (pinfunction "2_2") (pintype "passive"))
    )
    (net (code "14") (name "IN-TIA") (class "Default")
      (node (ref "C20") (pin "1") (pinfunction "1_1") (pintype "passive"))
      (node (ref "C21") (pin "1") (pinfunction "1_1") (pintype "passive"))
      (node (ref "C22") (pin "1") (pinfunction "1_1") (pintype "passive"))
      (node (ref "C23") (pin "1") (pinfunction "1_1") (pintype "passive"))
      (node (ref "R14") (pin "2") (pinfunction "2_2") (pintype "passive"))
      (node (ref "R20") (pin "2") (pinfunction "2_2") (pintype "passive"))
      (node (ref "R27") (pin "2") (pinfunction "2_2") (pintype "passive"))
      (node (ref "R30") (pin "2") (pinfunction "2_2") (pintype "passive"))
      (node (ref "RELAY") (pin "12") (pinfunction "OUT_12") (pintype "bidirectional"))
      (node (ref "U$12") (pin "2") (pinfunction "-IN_2") (pintype "bidirectional"))
    )
    (net (code "15") (name "IN3") (class "Default")
      (node (ref "MCDC01") (pin "1") (pinfunction "IN3_1") (pintype "bidirectional"))
      (node (ref "RELAY") (pin "10") (pinfunction "OUT1_10") (pintype "bidirectional"))
    )
    (net (code "16") (name "INT_RDY") (class "Default")
      (node (ref "U$13") (pin "13/D10") (pinfunction "D10_13/D10") (pintype "bidirectional"))
      (node (ref "U$3") (pin "7") (pinfunction "7_7") (pintype "bidirectional"))
    )
    (net (code "17") (name "LITE") (class "Default")
      (node (ref "DISPLAY") (pin "10") (pinfunction "LITE_10") (pintype "bidirectional"))
      (node (ref "U$13") (pin "6/D3") (pinfunction "D3_6/D3") (pintype "bidirectional"))
    )
    (net (code "18") (name "MISO") (class "Default")
      (node (ref "DISPLAY") (pin "9") (pinfunction "MISO_9") (pintype "bidirectional"))
      (node (ref "U$13") (pin "1/D12/MISO") (pinfunction "D12_1/D12/MISO") (pintype "bidirectional"))
    )
    (net (code "19") (name "MOSI") (class "Default")
      (node (ref "DISPLAY") (pin "7") (pinfunction "MOSI_7") (pintype "bidirectional"))
      (node (ref "U$13") (pin "4/D11/MOSI") (pinfunction "D11_4/D11/MOSI") (pintype "bidirectional"))
    )
    (net (code "20") (name "MOSI_I2C_ADD") (class "Default")
      (node (ref "U$13") (pin "14/D11/MOSI") (pinfunction "D11_14/D11/MOSI") (pintype "bidirectional"))
      (node (ref "U$3") (pin "10") (pinfunction "10_10") (pintype "bidirectional"))
    )
    (net (code "21") (name "Net-(LDO1-BYP)") (class "Default")
      (node (ref "C37") (pin "1") (pinfunction "1_1") (pintype "passive"))
      (node (ref "LDO1") (pin "4") (pinfunction "BYP_4") (pintype "bidirectional"))
    )
    (net (code "22") (name "Net-(LDO1-OUT)") (class "Default")
      (node (ref "C37") (pin "2") (pinfunction "2_2") (pintype "passive"))
      (node (ref "C38") (pin "2") (pinfunction "2_2") (pintype "passive"))
      (node (ref "C39") (pin "2") (pinfunction "2_2") (pintype "passive"))
      (node (ref "LDO1") (pin "5") (pinfunction "OUT_5") (pintype "bidirectional"))
      (node (ref "LR3") (pin "1") (pinfunction "1_1") (pintype "passive"))
    )
    (net (code "23") (name "Net-(MCDC01-REXT)") (class "Default")
      (node (ref "MCDC01") (pin "5") (pinfunction "REXT_5") (pintype "bidirectional"))
      (node (ref "R22") (pin "1") (pinfunction "1_1") (pintype "passive"))
    )
    (net (code "24") (name "Net-(MCDC01-VPD)") (class "Default")
      (node (ref "C35") (pin "2") (pinfunction "2_2") (pintype "passive"))
      (node (ref "MCDC01") (pin "16") (pinfunction "VPD_16") (pintype "bidirectional"))
    )
    (net (code "25") (name "Net-(R7-A)") (class "Default")
      (node (ref "R6") (pin "2") (pinfunction "2_2") (pintype "passive"))
      (node (ref "R7") (pin "1") (pinfunction "A_1") (pintype "passive"))
    )
    (net (code "26") (name "Net-(R8-S)") (class "Default")
      (node (ref "R8") (pin "2") (pinfunction "S_2") (pintype "passive"))
      (node (ref "R9") (pin "1") (pinfunction "1_1") (pintype "passive"))
    )
    (net (code "27") (name "Net-(R10-Pad1)") (class "Default")
      (node (ref "R10") (pin "1") (pinfunction "1_1") (pintype "passive"))
      (node (ref "R11") (pin "2") (pinfunction "2_2") (pintype "passive"))
      (node (ref "R9") (pin "2") (pinfunction "2_2") (pintype "passive"))
    )
    (net (code "28") (name "Net-(R16-S)") (class "Default")
      (node (ref "R16") (pin "2") (pinfunction "S_2") (pintype "passive"))
      (node (ref "R17") (pin "1") (pinfunction "1_1") (pintype "passive"))
    )
    (net (code "29") (name "Net-(R17-Pad2)") (class "Default")
      (node (ref "R17") (pin "2") (pinfunction "2_2") (pintype "passive"))
      (node (ref "R18") (pin "1") (pinfunction "1_1") (pintype "passive"))
      (node (ref "R19") (pin "2") (pinfunction "2_2") (pintype "passive"))
    )
    (net (code "30") (name "Net-(RELAY-IN)") (class "Default")
      (node (ref "RELAY") (pin "7") (pinfunction "IN_7") (pintype "bidirectional"))
      (node (ref "U$8") (pin "SIG_T") (pinfunction "SIGNAL_SIG_T") (pintype "bidirectional"))
    )
    (net (code "31") (name "Net-(U$10-+IN)") (class "Default")
      (node (ref "C14") (pin "2") (pinfunction "2_2") (pintype "passive"))
      (node (ref "R10") (pin "2") (pinfunction "2_2") (pintype "passive"))
      (node (ref "U$10") (pin "3") (pinfunction "+IN_3") (pintype "bidirectional"))
    )
    (net (code "32") (name "Net-(U$10-OUT)") (class "Default")
      (node (ref "C5") (pin "2") (pinfunction "2_2") (pintype "passive"))
      (node (ref "D1") (pin "C") (pinfunction "C_C") (pintype "passive"))
      (node (ref "R1") (pin "2") (pinfunction "2_2") (pintype "passive"))
      (node (ref "U$10") (pin "6") (pinfunction "OUT_6") (pintype "bidirectional"))
    )
    (net (code "33") (name "Net-(U$11-+VOUT)") (class "Default")
      (node (ref "C4") (pin "2") (pinfunction "2_2") (pintype "passive"))
      (node (ref "U$11") (pin "6") (pinfunction "+VOUT_6") (pintype "bidirectional"))
      (node (ref "U$4") (pin "P$1") (pinfunction "1_P$1") (pintype "bidirectional"))
    )
    (net (code "34") (name "Net-(U$11--VOUT)") (class "Default")
      (node (ref "C26") (pin "1") (pinfunction "1_1") (pintype "passive"))
      (node (ref "U$11") (pin "4") (pinfunction "-VOUT_4") (pintype "bidirectional"))
      (node (ref "U$2") (pin "P$1") (pinfunction "1_P$1") (pintype "bidirectional"))
    )
    (net (code "35") (name "Net-(U$12-+IN)") (class "Default")
      (node (ref "C15") (pin "2") (pinfunction "2_2") (pintype "passive"))
      (node (ref "R18") (pin "2") (pinfunction "2_2") (pintype "passive"))
      (node (ref "U$12") (pin "3") (pinfunction "+IN_3") (pintype "bidirectional"))
    )
    (net (code "36") (name "Net-(U$14-FB)") (class "Default")
      (node (ref "R13") (pin "2") (pinfunction "2_2") (pintype "passive"))
      (node (ref "R23") (pin "1") (pinfunction "1_1") (pintype "passive"))
      (node (ref "U$14") (pin "5") (pinfunction "FB_5") (pintype "bidirectional"))
    )
    (net (code "37") (name "Net-(U$14-PG)") (class "Default")
      (node (ref "R12") (pin "2") (pinfunction "2_2") (pintype "passive"))
      (node (ref "U$14") (pin "8") (pinfunction "PG_8") (pintype "bidirectional"))
    )
    (net (code "38") (name "Net-(U$14-SW)") (class "Default")
      (node (ref "U$14") (pin "7") (pinfunction "SW_7") (pintype "bidirectional"))
      (node (ref "U$9") (pin "1") (pinfunction "1_1") (pintype "bidirectional"))
    )
    (net (code "39") (name "Net-(U$14-VOS)") (class "Default")
      (node (ref "C28") (pin "2") (pinfunction "2_2") (pintype "passive"))
      (node (ref "D2") (pin "A") (pinfunction "A_A") (pintype "passive"))
      (node (ref "R12") (pin "1") (pinfunction "1_1") (pintype "passive"))
      (node (ref "R13") (pin "1") (pinfunction "1_1") (pintype "passive"))
      (node (ref "U$14") (pin "6") (pinfunction "VOS_6") (pintype "bidirectional"))
      (node (ref "U$9") (pin "2") (pinfunction "2_2") (pintype "bidirectional"))
    )
    (net (code "40") (name "Net-(VFC-COMP_INPUT)") (class "Default")
      (node (ref "R1") (pin "1") (pinfunction "1_1") (pintype "passive"))
      (node (ref "VFC") (pin "7") (pinfunction "COMP_INPUT_7") (pintype "bidirectional"))
    )
    (net (code "41") (name "Net-(VFC-REF_OUT)") (class "Default")
      (node (ref "R6") (pin "1") (pinfunction "1_1") (pintype "passive"))
      (node (ref "VFC") (pin "2") (pinfunction "REF_OUT_2") (pintype "bidirectional"))
    )
    (net (code "42") (name "Net-(VFC-R{slash}C)") (class "Default")
      (node (ref "C6") (pin "1") (pinfunction "1_1") (pintype "passive"))
      (node (ref "R2") (pin "1") (pinfunction "1_1") (pintype "passive"))
      (node (ref "VFC") (pin "5") (pinfunction "R/C_5") (pintype "bidirectional"))
    )
    (net (code "43") (name "Net-(VFC-THRESHOLD)") (class "Default")
      (node (ref "C9") (pin "1") (pinfunction "1_1") (pintype "passive"))
      (node (ref "R4") (pin "1") (pinfunction "1_1") (pintype "passive"))
      (node (ref "R5") (pin "2") (pinfunction "2_2") (pintype "passive"))
      (node (ref "VFC") (pin "6") (pinfunction "THRESHOLD_6") (pintype "bidirectional"))
    )
    (net (code "44") (name "OUT_TIA") (class "Default")
      (node (ref "C5") (pin "1") (pinfunction "1_1") (pintype "passive"))
      (node (ref "R15") (pin "2") (pinfunction "2_2") (pintype "passive"))
      (node (ref "U$10") (pin "2") (pinfunction "-IN_2") (pintype "bidirectional"))
      (node (ref "VFC") (pin "1") (pinfunction "CURRENT_OUT_1") (pintype "bidirectional"))
    )
    (net (code "45") (name "READY") (class "Default")
      (node (ref "MCDC01") (pin "12") (pinfunction "RDY_12") (pintype "bidirectional"))
      (node (ref "U$13") (pin "5/D2") (pinfunction "D2_5/D2") (pintype "bidirectional"))
    )
    (net (code "46") (name "S1") (class "Default")
      (node (ref "C22") (pin "2") (pinfunction "2_2") (pintype "passive"))
      (node (ref "R30") (pin "1") (pinfunction "1_1") (pintype "passive"))
      (node (ref "U$1") (pin "4") (pinfunction "S1_4") (pintype "bidirectional"))
    )
    (net (code "47") (name "S2") (class "Default")
      (node (ref "C21") (pin "2") (pinfunction "2_2") (pintype "passive"))
      (node (ref "R14") (pin "1") (pinfunction "1_1") (pintype "passive"))
      (node (ref "U$1") (pin "5") (pinfunction "S2_5") (pintype "bidirectional"))
    )
    (net (code "48") (name "S3") (class "Default")
      (node (ref "C23") (pin "2") (pinfunction "2_2") (pintype "passive"))
      (node (ref "R20") (pin "1") (pinfunction "1_1") (pintype "passive"))
      (node (ref "U$1") (pin "11") (pinfunction "S3_11") (pintype "bidirectional"))
    )
    (net (code "49") (name "S4") (class "Default")
      (node (ref "C20") (pin "2") (pinfunction "2_2") (pintype "passive"))
      (node (ref "R27") (pin "1") (pinfunction "1_1") (pintype "passive"))
      (node (ref "U$1") (pin "10") (pinfunction "S4_10") (pintype "bidirectional"))
    )
    (net (code "50") (name "SCL") (class "Default")
      (node (ref "U$13") (pin "7/A5") (pinfunction "A5_7/A5") (pintype "bidirectional"))
      (node (ref "U$3") (pin "6") (pinfunction "6_6") (pintype "bidirectional"))
    )
    (net (code "51") (name "SDA") (class "Default")
      (node (ref "U$13") (pin "8/A4") (pinfunction "A4_8/A4") (pintype "bidirectional"))
      (node (ref "U$3") (pin "5") (pinfunction "5_5") (pintype "bidirectional"))
    )
    (net (code "52") (name "SOFT_SCL") (class "Default")
      (node (ref "MCDC01") (pin "11") (pinfunction "SCL_11") (pintype "bidirectional"))
      (node (ref "R32") (pin "1") (pinfunction "1_1") (pintype "passive"))
      (node (ref "U$13") (pin "10/D7") (pinfunction "D7_10/D7") (pintype "bidirectional"))
      (node (ref "U$7") (pin "6") (pinfunction "SCL_6") (pintype "bidirectional"))
    )
    (net (code "53") (name "SOFT_SDA") (class "Default")
      (node (ref "MCDC01") (pin "10") (pinfunction "SDA_10") (pintype "bidirectional"))
      (node (ref "R31") (pin "1") (pinfunction "1_1") (pintype "passive"))
      (node (ref "U$13") (pin "9/D6") (pinfunction "D6_9/D6") (pintype "bidirectional"))
      (node (ref "U$7") (pin "7") (pinfunction "SDA_7") (pintype "bidirectional"))
    )
    (net (code "54") (name "SPI_CLK_I2C_ADD") (class "Default")
      (node (ref "U$13") (pin "15/D13") (pinfunction "D13_15/D13") (pintype "bidirectional"))
      (node (ref "U$3") (pin "9") (pinfunction "9_9") (pintype "bidirectional"))
    )
    (net (code "55") (name "SPI_SCK") (class "Default")
      (node (ref "DISPLAY") (pin "8") (pinfunction "SCK_8") (pintype "bidirectional"))
      (node (ref "U$13") (pin "3/D13/SCK") (pinfunction "D13_3/D13/SCK") (pintype "bidirectional"))
    )
    (net (code "56") (name "SW_A0") (class "Default")
      (node (ref "U$1") (pin "1") (pinfunction "A0_1") (pintype "bidirectional"))
      (node (ref "U$13") (pin "11/A1") (pinfunction "A1_11/A1") (pintype "bidirectional"))
    )
    (net (code "57") (name "SW_A1") (class "Default")
      (node (ref "U$1") (pin "14") (pinfunction "A1_14") (pintype "bidirectional"))
      (node (ref "U$13") (pin "12/A0") (pinfunction "A0_12/A0") (pintype "bidirectional"))
    )
    (net (code "58") (name "SW_EN") (class "Default")
      (node (ref "U$1") (pin "2") (pinfunction "EN_2") (pintype "bidirectional"))
      (node (ref "U$13") (pin "10/A2") (pinfunction "A2_10/A2") (pintype "bidirectional"))
      (node (ref "U$6") (pin "6") (pinfunction "IN_6") (pintype "bidirectional"))
    )
    (net (code "59") (name "TFT_CS") (class "Default")
      (node (ref "DISPLAY") (pin "6") (pinfunction "TFT_CS_6") (pintype "bidirectional"))
      (node (ref "U$13") (pin "11/D8") (pinfunction "D8_11/D8") (pintype "bidirectional"))
    )
    (net (code "60") (name "VDD") (class "Default")
      (node (ref "C33") (pin "2") (pinfunction "2_2") (pintype "passive"))
      (node (ref "LR3") (pin "2") (pinfunction "2_2") (pintype "passive"))
      (node (ref "LR4") (pin "2") (pinfunction "2_2") (pintype "passive"))
      (node (ref "MCDC01") (pin "14") (pinfunction "VDD_14") (pintype "bidirectional"))
    )
    (net (code "61") (name "VDDA") (class "Default")
      (node (ref "C34") (pin "2") (pinfunction "2_2") (pintype "passive"))
      (node (ref "LR4") (pin "1") (pinfunction "1_1") (pintype "passive"))
      (node (ref "MCDC01") (pin "15") (pinfunction "VDDA_15") (pintype "bidirectional"))
    )
    (net (code "62") (name "VUSB5V") (class "Default")
      (node (ref "C1") (pin "2") (pinfunction "2_2") (pintype "passive"))
      (node (ref "C36") (pin "2") (pinfunction "2_2") (pintype "passive"))
      (node (ref "D2") (pin "C") (pinfunction "C_C") (pintype "passive"))
      (node (ref "DISPLAY") (pin "2") (pinfunction "VCC_2") (pintype "bidirectional"))
      (node (ref "DISPLAY") (pin "3") (pinfunction "RESET_3") (pintype "bidirectional"))
      (node (ref "LDO1") (pin "1") (pinfunction "IN_1") (pintype "bidirectional"))
      (node (ref "LDO1") (pin "3") (pinfunction "SHDN_3") (pintype "bidirectional"))
      (node (ref "R3") (pin "2") (pinfunction "2_2") (pintype "passive"))
      (node (ref "R31") (pin "2") (pinfunction "2_2") (pintype "passive"))
      (node (ref "R32") (pin "2") (pinfunction "2_2") (pintype "passive"))
      (node (ref "U$11") (pin "1") (pinfunction "+VIN_1") (pintype "bidirectional"))
      (node (ref "U$13") (pin "4/+5V") (pinfunction "5V_4/+5V") (pintype "bidirectional"))
      (node (ref "U$6") (pin "5") (pinfunction "V+_5") (pintype "bidirectional"))
      (node (ref "U$7") (pin "8") (pinfunction "VCC_8") (pintype "bidirectional"))
      (node (ref "U$8") (pin "GND_B@1") (pinfunction "POTENZIAL_GND_B@1") (pintype "bidirectional"))
      (node (ref "U$8") (pin "GND_B@2") (pinfunction "POTENZIAL_GND_B@2") (pintype "bidirectional"))
      (node (ref "U1") (pin "H1") (pinfunction "H+_H1") (pintype "bidirectional"))
      (node (ref "U1") (pin "V1") (pinfunction "V+_V1") (pintype "bidirectional"))
    )
    (net (code "63") (name "V_IN_BUCK") (class "Default")
      (node (ref "C27") (pin "2") (pinfunction "2_2") (pintype "passive"))
      (node (ref "C29") (pin "2") (pinfunction "2_2") (pintype "passive"))
      (node (ref "C30") (pin "2") (pinfunction "2_2") (pintype "passive"))
      (node (ref "U$14") (pin "2") (pinfunction "VIN_2") (pintype "bidirectional"))
      (node (ref "U$14") (pin "3") (pinfunction "EN_3") (pintype "bidirectional"))
      (node (ref "U$3") (pin "8") (pinfunction "8_8") (pintype "bidirectional"))
    )
    (net (code "64") (name "X_RELAY") (class "Default")
      (node (ref "D5") (pin "C") (pinfunction "C_C") (pintype "passive"))
      (node (ref "RELAY") (pin "6") (pinfunction "V1+_6") (pintype "bidirectional"))
      (node (ref "U$7") (pin "3") (pinfunction "P2_3") (pintype "bidirectional"))
      (node (ref "U$7") (pin "5") (pinfunction "P3_5") (pintype "bidirectional"))
    )
    (net (code "65") (name "Y_RELAY") (class "Default")
      (node (ref "D6") (pin "C") (pinfunction "C_C") (pintype "passive"))
      (node (ref "RELAY") (pin "1") (pinfunction "V+_1") (pintype "bidirectional"))
      (node (ref "U$7") (pin "1") (pinfunction "P0_1") (pintype "bidirectional"))
      (node (ref "U$7") (pin "2") (pinfunction "P1_2") (pintype "bidirectional"))
    )
    (net (code "66") (name "unconnected-(MCDC01-IN0-Pad4)") (class "Default")
      (node (ref "MCDC01") (pin "4") (pinfunction "IN0_4") (pintype "bidirectional"))
    )
    (net (code "67") (name "unconnected-(MCDC01-IN1-Pad3)") (class "Default")
      (node (ref "MCDC01") (pin "3") (pinfunction "IN1_3") (pintype "bidirectional"))
    )
    (net (code "68") (name "unconnected-(MCDC01-IN2-Pad2)") (class "Default")
      (node (ref "MCDC01") (pin "2") (pinfunction "IN2_2") (pintype "bidirectional"))
    )
    (net (code "69") (name "unconnected-(MCDC01-SYN-Pad13)") (class "Default")
      (node (ref "MCDC01") (pin "13") (pinfunction "SYN_13") (pintype "bidirectional"))
    )
    (net (code "70") (name "unconnected-(R7-E-Pad3)") (class "Default")
      (node (ref "R7") (pin "3") (pinfunction "E_3") (pintype "passive"))
    )
    (net (code "71") (name "unconnected-(U$1-NC-Pad7)") (class "Default")
      (node (ref "U$1") (pin "7") (pinfunction "NC_7") (pintype "bidirectional"))
    )
    (net (code "72") (name "unconnected-(U$1-NC1-Pad8)") (class "Default")
      (node (ref "U$1") (pin "8") (pinfunction "NC1_8") (pintype "bidirectional"))
    )
    (net (code "73") (name "unconnected-(U$1-NC2-Pad9)") (class "Default")
      (node (ref "U$1") (pin "9") (pinfunction "NC2_9") (pintype "bidirectional"))
    )
    (net (code "74") (name "unconnected-(U$3-Pad2)") (class "Default")
      (node (ref "U$3") (pin "2") (pinfunction "2_2") (pintype "bidirectional"))
    )
    (net (code "75") (name "unconnected-(U$3-Pad3)") (class "Default")
      (node (ref "U$3") (pin "3") (pinfunction "3_3") (pintype "bidirectional"))
    )
    (net (code "76") (name "unconnected-(U$3-Pad4)") (class "Default")
      (node (ref "U$3") (pin "4") (pinfunction "4_4") (pintype "bidirectional"))
    )
    (net (code "77") (name "unconnected-(U$6-NC-Pad3)") (class "Default")
      (node (ref "U$6") (pin "3") (pinfunction "NC_3") (pintype "bidirectional"))
    )
    (net (code "78") (name "unconnected-(U$10-NC-Pad1)") (class "Default")
      (node (ref "U$10") (pin "1") (pinfunction "NC_1") (pintype "bidirectional"))
    )
    (net (code "79") (name "unconnected-(U$10-NC1-Pad8)") (class "Default")
      (node (ref "U$10") (pin "8") (pinfunction "NC1_8") (pintype "bidirectional"))
    )
    (net (code "80") (name "unconnected-(U$10-NC2-Pad5)") (class "Default")
      (node (ref "U$10") (pin "5") (pinfunction "NC2_5") (pintype "bidirectional"))
    )
    (net (code "81") (name "unconnected-(U$12-NC-Pad1)") (class "Default")
      (node (ref "U$12") (pin "1") (pinfunction "NC_1") (pintype "bidirectional"))
    )
    (net (code "82") (name "unconnected-(U$12-NC1-Pad8)") (class "Default")
      (node (ref "U$12") (pin "8") (pinfunction "NC1_8") (pintype "bidirectional"))
    )
    (net (code "83") (name "unconnected-(U$12-NC2-Pad5)") (class "Default")
      (node (ref "U$12") (pin "5") (pinfunction "NC2_5") (pintype "bidirectional"))
    )
  )
)
